# motor_shield__SD_v1_1.net
KiCad netlist of a schematic drawn in EAGLE
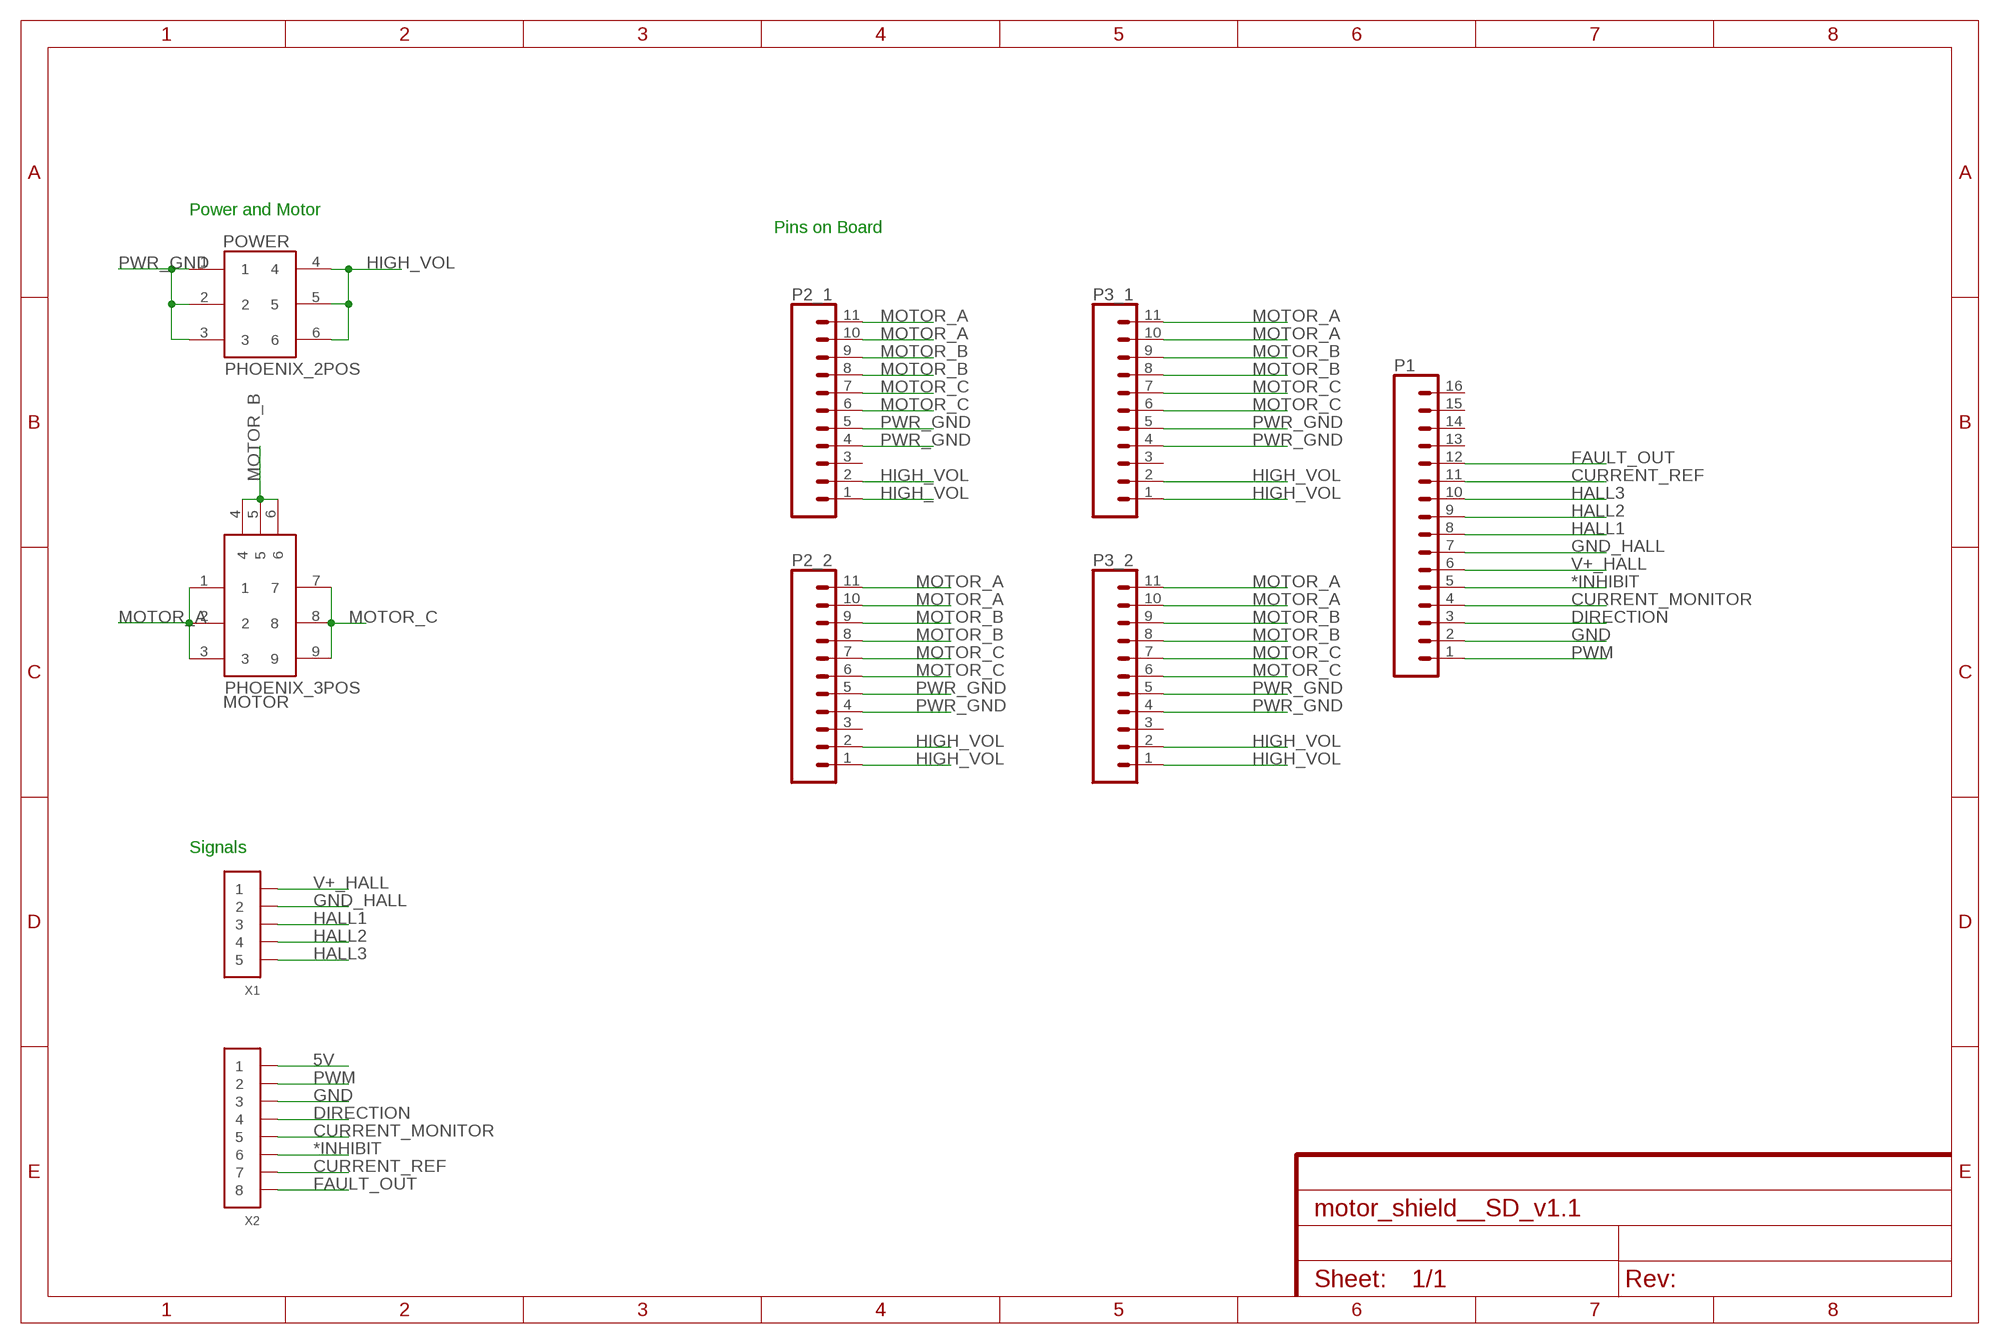
[diagram p0: schematic, sheet 1]

(export (version "E")
  (design (tool "Eeschema 10.0.6"))
  (components
    (comp (ref "MOTOR")
      (value "PHOENIX_3POS")
      (footprint "eagle-import:PHOENIX_3POS")
      (libsource (lib "eagle-import") (part "PHOENIX_3POS"))
    )
    (comp (ref "P1")
      (value "CONN_16LOCK")
      (footprint "eagle-import:1X16_LOCK")
      (libsource (lib "eagle-import") (part "CONN_16LOCK"))
    )
    (comp (ref "P2_1")
      (value "CONN_11")
      (footprint "eagle-import:1X11")
      (libsource (lib "eagle-import") (part "CONN_11"))
    )
    (comp (ref "P2_2")
      (value "CONN_11")
      (footprint "eagle-import:1X11")
      (libsource (lib "eagle-import") (part "CONN_11"))
    )
    (comp (ref "P3_1")
      (value "CONN_11")
      (footprint "eagle-import:1X11")
      (libsource (lib "eagle-import") (part "CONN_11"))
    )
    (comp (ref "P3_2")
      (value "CONN_11")
      (footprint "eagle-import:1X11")
      (libsource (lib "eagle-import") (part "CONN_11"))
    )
    (comp (ref "POWER")
      (value "PHOENIX_2POS")
      (footprint "eagle-import:PHOENIX_2POS")
      (libsource (lib "eagle-import") (part "PHOENIX_2POS"))
    )
    (comp (ref "X1")
      (value "CONN_5-1-53261")
      (footprint "eagle-import:PB-53261-05")
      (libsource (lib "eagle-import") (part "CONN_5-1-53261"))
    )
    (comp (ref "X2")
      (value "CONN_8-1-53261")
      (footprint "eagle-import:PB-53261-08")
      (libsource (lib "eagle-import") (part "CONN_8-1-53261"))
    )
  )
  (nets
    (net (code "1") (name "/*INHIBIT") (class "Default")
      (node (ref "P1") (pin "5") (pinfunction "5_5") (pintype "passive"))
      (node (ref "X2") (pin "6") (pinfunction "6_6") (pintype "bidirectional"))
    )
    (net (code "2") (name "/5V") (class "Default")
      (node (ref "X2") (pin "1") (pinfunction "1_1") (pintype "bidirectional"))
    )
    (net (code "3") (name "/CURRENT_MONITOR") (class "Default")
      (node (ref "P1") (pin "4") (pinfunction "4_4") (pintype "passive"))
      (node (ref "X2") (pin "5") (pinfunction "5_5") (pintype "bidirectional"))
    )
    (net (code "4") (name "/CURRENT_REF") (class "Default")
      (node (ref "P1") (pin "11") (pinfunction "11_11") (pintype "passive"))
      (node (ref "X2") (pin "7") (pinfunction "7_7") (pintype "bidirectional"))
    )
    (net (code "5") (name "/DIRECTION") (class "Default")
      (node (ref "P1") (pin "3") (pinfunction "3_3") (pintype "passive"))
      (node (ref "X2") (pin "4") (pinfunction "4_4") (pintype "bidirectional"))
    )
    (net (code "6") (name "/FAULT_OUT") (class "Default")
      (node (ref "P1") (pin "12") (pinfunction "12_12") (pintype "passive"))
      (node (ref "X2") (pin "8") (pinfunction "8_8") (pintype "bidirectional"))
    )
    (net (code "7") (name "/GND") (class "Default")
      (node (ref "P1") (pin "2") (pinfunction "2_2") (pintype "passive"))
      (node (ref "X2") (pin "3") (pinfunction "3_3") (pintype "bidirectional"))
    )
    (net (code "8") (name "/GND_HALL") (class "Default")
      (node (ref "P1") (pin "7") (pinfunction "7_7") (pintype "passive"))
      (node (ref "X1") (pin "2") (pinfunction "2_2") (pintype "bidirectional"))
    )
    (net (code "9") (name "/HALL1") (class "Default")
      (node (ref "P1") (pin "8") (pinfunction "8_8") (pintype "passive"))
      (node (ref "X1") (pin "3") (pinfunction "3_3") (pintype "bidirectional"))
    )
    (net (code "10") (name "/HALL2") (class "Default")
      (node (ref "P1") (pin "9") (pinfunction "9_9") (pintype "passive"))
      (node (ref "X1") (pin "4") (pinfunction "4_4") (pintype "bidirectional"))
    )
    (net (code "11") (name "/HALL3") (class "Default")
      (node (ref "P1") (pin "10") (pinfunction "10_10") (pintype "passive"))
      (node (ref "X1") (pin "5") (pinfunction "5_5") (pintype "bidirectional"))
    )
    (net (code "12") (name "/HIGH_VOL") (class "Default")
      (node (ref "P2_1") (pin "1") (pinfunction "1_1") (pintype "passive"))
      (node (ref "P2_1") (pin "2") (pinfunction "2_2") (pintype "passive"))
      (node (ref "P2_2") (pin "1") (pinfunction "1_1") (pintype "passive"))
      (node (ref "P2_2") (pin "2") (pinfunction "2_2") (pintype "passive"))
      (node (ref "P3_1") (pin "1") (pinfunction "1_1") (pintype "passive"))
      (node (ref "P3_1") (pin "2") (pinfunction "2_2") (pintype "passive"))
      (node (ref "P3_2") (pin "1") (pinfunction "1_1") (pintype "passive"))
      (node (ref "P3_2") (pin "2") (pinfunction "2_2") (pintype "passive"))
      (node (ref "POWER") (pin "4") (pinfunction "4_4") (pintype "bidirectional"))
      (node (ref "POWER") (pin "5") (pinfunction "5_5") (pintype "bidirectional"))
      (node (ref "POWER") (pin "6") (pinfunction "6_6") (pintype "bidirectional"))
    )
    (net (code "13") (name "/MOTOR_A") (class "Default")
      (node (ref "MOTOR") (pin "1") (pinfunction "1_1") (pintype "bidirectional"))
      (node (ref "MOTOR") (pin "2") (pinfunction "2_2") (pintype "bidirectional"))
      (node (ref "MOTOR") (pin "3") (pinfunction "3_3") (pintype "bidirectional"))
      (node (ref "P2_1") (pin "10") (pinfunction "10_10") (pintype "passive"))
      (node (ref "P2_1") (pin "11") (pinfunction "11_11") (pintype "passive"))
      (node (ref "P2_2") (pin "10") (pinfunction "10_10") (pintype "passive"))
      (node (ref "P2_2") (pin "11") (pinfunction "11_11") (pintype "passive"))
      (node (ref "P3_1") (pin "10") (pinfunction "10_10") (pintype "passive"))
      (node (ref "P3_1") (pin "11") (pinfunction "11_11") (pintype "passive"))
      (node (ref "P3_2") (pin "10") (pinfunction "10_10") (pintype "passive"))
      (node (ref "P3_2") (pin "11") (pinfunction "11_11") (pintype "passive"))
    )
    (net (code "14") (name "/MOTOR_B") (class "Default")
      (node (ref "MOTOR") (pin "4") (pinfunction "4_4") (pintype "bidirectional"))
      (node (ref "MOTOR") (pin "5") (pinfunction "5_5") (pintype "bidirectional"))
      (node (ref "MOTOR") (pin "6") (pinfunction "6_6") (pintype "bidirectional"))
      (node (ref "P2_1") (pin "8") (pinfunction "8_8") (pintype "passive"))
      (node (ref "P2_1") (pin "9") (pinfunction "9_9") (pintype "passive"))
      (node (ref "P2_2") (pin "8") (pinfunction "8_8") (pintype "passive"))
      (node (ref "P2_2") (pin "9") (pinfunction "9_9") (pintype "passive"))
      (node (ref "P3_1") (pin "8") (pinfunction "8_8") (pintype "passive"))
      (node (ref "P3_1") (pin "9") (pinfunction "9_9") (pintype "passive"))
      (node (ref "P3_2") (pin "8") (pinfunction "8_8") (pintype "passive"))
      (node (ref "P3_2") (pin "9") (pinfunction "9_9") (pintype "passive"))
    )
    (net (code "15") (name "/MOTOR_C") (class "Default")
      (node (ref "MOTOR") (pin "7") (pinfunction "7_7") (pintype "bidirectional"))
      (node (ref "MOTOR") (pin "8") (pinfunction "8_8") (pintype "bidirectional"))
      (node (ref "MOTOR") (pin "9") (pinfunction "9_9") (pintype "bidirectional"))
      (node (ref "P2_1") (pin "6") (pinfunction "6_6") (pintype "passive"))
      (node (ref "P2_1") (pin "7") (pinfunction "7_7") (pintype "passive"))
      (node (ref "P2_2") (pin "6") (pinfunction "6_6") (pintype "passive"))
      (node (ref "P2_2") (pin "7") (pinfunction "7_7") (pintype "passive"))
      (node (ref "P3_1") (pin "6") (pinfunction "6_6") (pintype "passive"))
      (node (ref "P3_1") (pin "7") (pinfunction "7_7") (pintype "passive"))
      (node (ref "P3_2") (pin "6") (pinfunction "6_6") (pintype "passive"))
      (node (ref "P3_2") (pin "7") (pinfunction "7_7") (pintype "passive"))
    )
    (net (code "16") (name "/PWM") (class "Default")
      (node (ref "P1") (pin "1") (pinfunction "1_1") (pintype "passive"))
      (node (ref "X2") (pin "2") (pinfunction "2_2") (pintype "bidirectional"))
    )
    (net (code "17") (name "/PWR_GND") (class "Default")
      (node (ref "P2_1") (pin "4") (pinfunction "4_4") (pintype "passive"))
      (node (ref "P2_1") (pin "5") (pinfunction "5_5") (pintype "passive"))
      (node (ref "P2_2") (pin "4") (pinfunction "4_4") (pintype "passive"))
      (node (ref "P2_2") (pin "5") (pinfunction "5_5") (pintype "passive"))
      (node (ref "P3_1") (pin "4") (pinfunction "4_4") (pintype "passive"))
      (node (ref "P3_1") (pin "5") (pinfunction "5_5") (pintype "passive"))
      (node (ref "P3_2") (pin "4") (pinfunction "4_4") (pintype "passive"))
      (node (ref "P3_2") (pin "5") (pinfunction "5_5") (pintype "passive"))
      (node (ref "POWER") (pin "1") (pinfunction "1_1") (pintype "bidirectional"))
      (node (ref "POWER") (pin "2") (pinfunction "2_2") (pintype "bidirectional"))
      (node (ref "POWER") (pin "3") (pinfunction "3_3") (pintype "bidirectional"))
    )
    (net (code "18") (name "/V+_HALL") (class "Default")
      (node (ref "P1") (pin "6") (pinfunction "6_6") (pintype "passive"))
      (node (ref "X1") (pin "1") (pinfunction "1_1") (pintype "bidirectional"))
    )
    (net (code "19") (name "unconnected-(P1-Pad13)") (class "Default")
      (node (ref "P1") (pin "13") (pinfunction "13_13") (pintype "passive"))
    )
    (net (code "20") (name "unconnected-(P1-Pad14)") (class "Default")
      (node (ref "P1") (pin "14") (pinfunction "14_14") (pintype "passive"))
    )
    (net (code "21") (name "unconnected-(P1-Pad15)") (class "Default")
      (node (ref "P1") (pin "15") (pinfunction "15_15") (pintype "passive"))
    )
    (net (code "22") (name "unconnected-(P1-Pad16)") (class "Default")
      (node (ref "P1") (pin "16") (pinfunction "16_16") (pintype "passive"))
    )
    (net (code "23") (name "unconnected-(P2_1-Pad3)") (class "Default")
      (node (ref "P2_1") (pin "3") (pinfunction "3_3") (pintype "passive"))
    )
    (net (code "24") (name "unconnected-(P2_2-Pad3)") (class "Default")
      (node (ref "P2_2") (pin "3") (pinfunction "3_3") (pintype "passive"))
    )
    (net (code "25") (name "unconnected-(P3_1-Pad3)") (class "Default")
      (node (ref "P3_1") (pin "3") (pinfunction "3_3") (pintype "passive"))
    )
    (net (code "26") (name "unconnected-(P3_2-Pad3)") (class "Default")
      (node (ref "P3_2") (pin "3") (pinfunction "3_3") (pintype "passive"))
    )
  )
)
